# BLDC_ESC.net
KiCad netlist of a schematic drawn in EAGLE
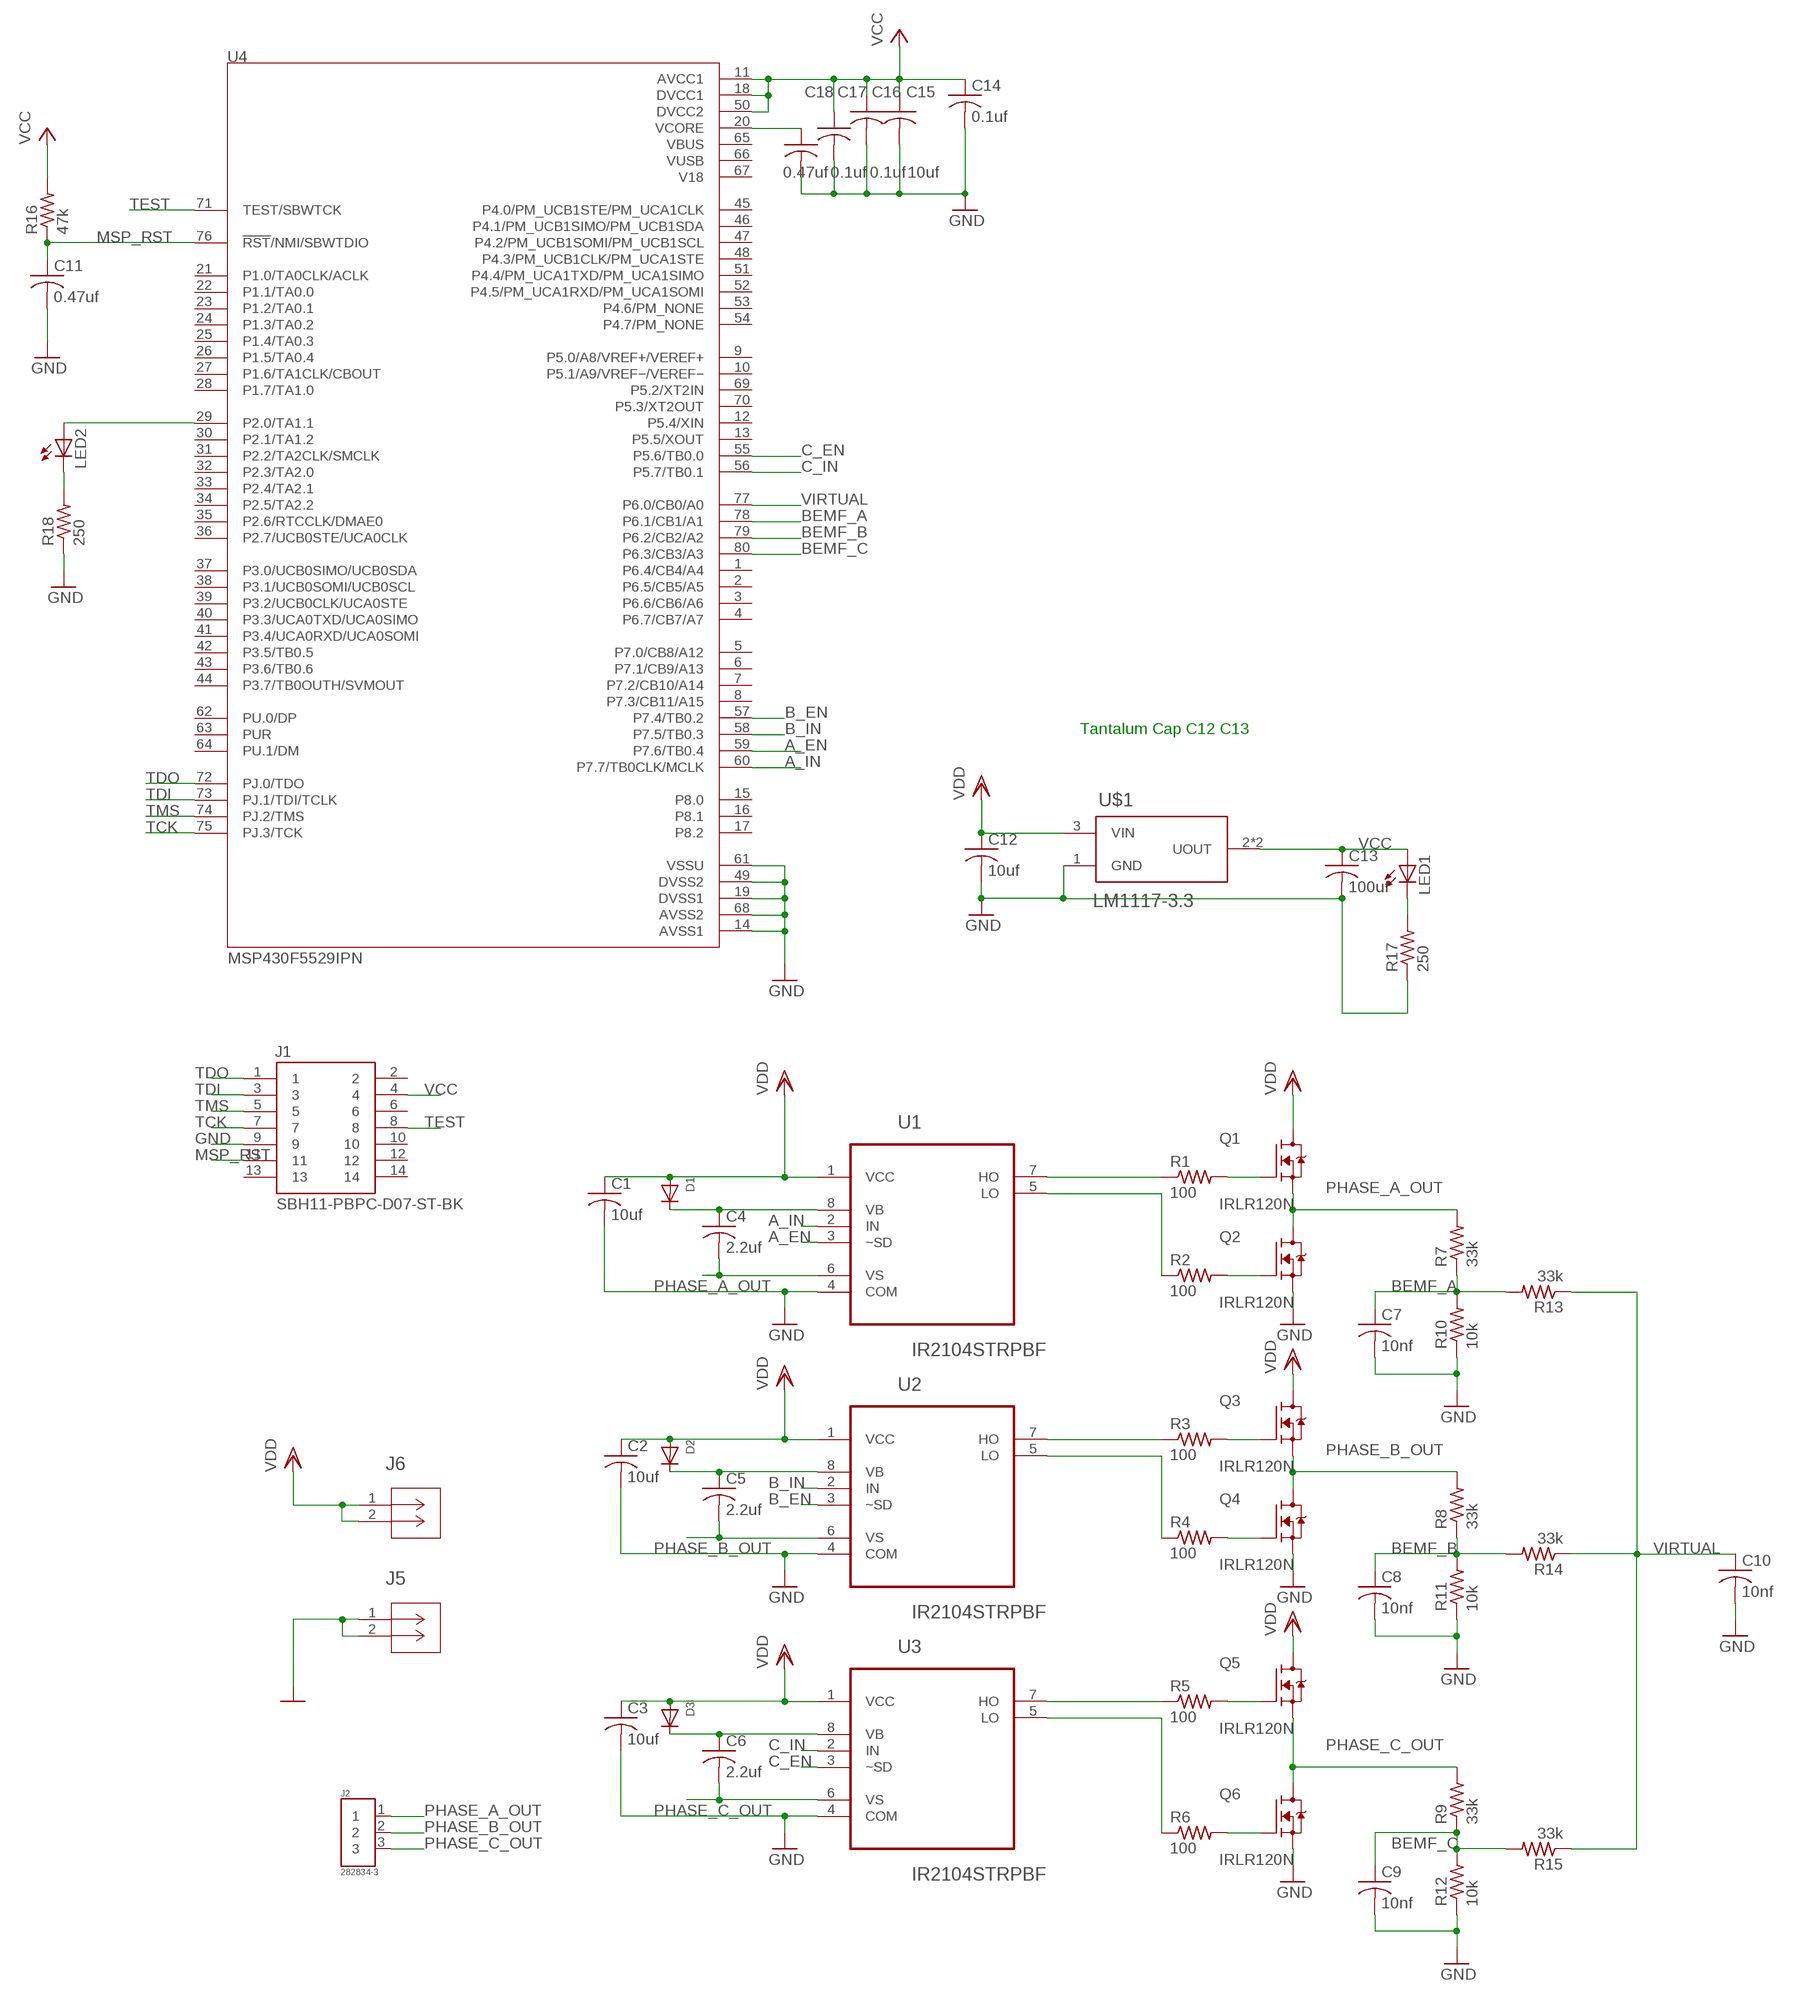
[diagram p0: schematic, sheet 1]

(export (version "E")
  (design (tool "Eeschema 10.0.6"))
  (components
    (comp (ref "C1")
      (value "10uf")
      (footprint "eagle-import:C0805K")
      (libsource (lib "eagle-import") (part "C-USC0805K"))
    )
    (comp (ref "C2")
      (value "10uf")
      (footprint "eagle-import:C0805K")
      (libsource (lib "eagle-import") (part "C-USC0805K"))
    )
    (comp (ref "C3")
      (value "10uf")
      (footprint "eagle-import:C0805K")
      (libsource (lib "eagle-import") (part "C-USC0805K"))
    )
    (comp (ref "C4")
      (value "2.2uf")
      (footprint "eagle-import:C0805K")
      (libsource (lib "eagle-import") (part "C-USC0805K"))
    )
    (comp (ref "C5")
      (value "2.2uf")
      (footprint "eagle-import:C0805K")
      (libsource (lib "eagle-import") (part "C-USC0805K"))
    )
    (comp (ref "C6")
      (value "2.2uf")
      (footprint "eagle-import:C0805K")
      (libsource (lib "eagle-import") (part "C-USC0805K"))
    )
    (comp (ref "C7")
      (value "10nf")
      (footprint "eagle-import:C0805")
      (libsource (lib "eagle-import") (part "rcl_334_C-USC0805"))
    )
    (comp (ref "C8")
      (value "10nf")
      (footprint "eagle-import:C0805")
      (libsource (lib "eagle-import") (part "rcl_334_C-USC0805"))
    )
    (comp (ref "C9")
      (value "10nf")
      (footprint "eagle-import:C0805")
      (libsource (lib "eagle-import") (part "rcl_334_C-USC0805"))
    )
    (comp (ref "C10")
      (value "10nf")
      (footprint "eagle-import:C0805")
      (libsource (lib "eagle-import") (part "rcl_334_C-USC0805"))
    )
    (comp (ref "C11")
      (value "0.47uf")
      (footprint "eagle-import:C0805")
      (libsource (lib "eagle-import") (part "rcl_334_C-USC0805"))
    )
    (comp (ref "C12")
      (value "10uf")
      (footprint "eagle-import:C0805")
      (libsource (lib "eagle-import") (part "C-USC0805"))
    )
    (comp (ref "C13")
      (value "100uf")
      (footprint "eagle-import:C0805")
      (libsource (lib "eagle-import") (part "C-USC0805"))
    )
    (comp (ref "C14")
      (value "0.1uf")
      (footprint "eagle-import:C0805")
      (libsource (lib "eagle-import") (part "C-USC0805"))
    )
    (comp (ref "C15")
      (value "10uf")
      (footprint "eagle-import:C0805")
      (libsource (lib "eagle-import") (part "C-USC0805"))
    )
    (comp (ref "C16")
      (value "0.1uf")
      (footprint "eagle-import:C0805")
      (libsource (lib "eagle-import") (part "C-USC0805"))
    )
    (comp (ref "C17")
      (value "0.1uf")
      (footprint "eagle-import:C0805")
      (libsource (lib "eagle-import") (part "C-USC0805"))
    )
    (comp (ref "C18")
      (value "0.47uf")
      (footprint "eagle-import:C0805")
      (libsource (lib "eagle-import") (part "C-USC0805"))
    )
    (comp (ref "D1")
      (value "DIODESOD-123")
      (footprint "eagle-import:SOD-123")
      (libsource (lib "eagle-import") (part "DIODESOD-123"))
    )
    (comp (ref "D2")
      (value "DIODESOD-123")
      (footprint "eagle-import:SOD-123")
      (libsource (lib "eagle-import") (part "DIODESOD-123"))
    )
    (comp (ref "D3")
      (value "DIODESOD-123")
      (footprint "eagle-import:SOD-123")
      (libsource (lib "eagle-import") (part "DIODESOD-123"))
    )
    (comp (ref "J1")
      (value "SBH11-PBPC-D07-ST-BK")
      (footprint "eagle-import:SULLINS_SBH11-PBPC-D07-ST-BK")
      (fields (field (name "DIGI-KEY_PART_NUMBER") "S9170-ND") (field (name "MF") "Sullins Connector"))
      (libsource (lib "eagle-import") (part "SBH11-PBPC-D07-ST-BK"))
    )
    (comp (ref "J2")
      (value "282834-3")
      (footprint "eagle-import:TE_282834-3")
      (fields (field (name "DIGI-KEY_PART_NUMBER") "A98334-ND") (field (name "MF") "TE Connectivity"))
      (libsource (lib "eagle-import") (part "282834-3"))
    )
    (comp (ref "J5")
      (value "105-1103-001")
      (footprint "eagle-import:CONN_105-1102-001")
      (fields (field (name "COPYRIGHT") "Copyright (C) 2018 Accelerated Designs. All rights reserved"))
      (libsource (lib "eagle-import") (part "105-1103-001"))
    )
    (comp (ref "J6")
      (value "105-1103-001")
      (footprint "eagle-import:CONN_105-1102-001")
      (fields (field (name "COPYRIGHT") "Copyright (C) 2018 Accelerated Designs. All rights reserved"))
      (libsource (lib "eagle-import") (part "105-1103-001"))
    )
    (comp (ref "LED1")
      (value "LEDCHIPLED_0805")
      (footprint "eagle-import:CHIPLED_0805")
      (libsource (lib "eagle-import") (part "LEDCHIPLED_0805"))
    )
    (comp (ref "LED2")
      (value "LEDCHIPLED_0805")
      (footprint "eagle-import:CHIPLED_0805")
      (libsource (lib "eagle-import") (part "LEDCHIPLED_0805"))
    )
    (comp (ref "Q1")
      (value "IRLR120N")
      (footprint "eagle-import:DPAK229P990X239-3N")
      (fields
        (field (name "DIGI-KEY_PART_NUMBER") "IRLR120NPBFCT-ND")
        (field (name "MF") "Infineon Technologies")
      )
      (libsource (lib "eagle-import") (part "IRLR120N"))
    )
    (comp (ref "Q2")
      (value "IRLR120N")
      (footprint "eagle-import:DPAK229P990X239-3N")
      (fields
        (field (name "DIGI-KEY_PART_NUMBER") "IRLR120NPBFCT-ND")
        (field (name "MF") "Infineon Technologies")
      )
      (libsource (lib "eagle-import") (part "IRLR120N"))
    )
    (comp (ref "Q3")
      (value "IRLR120N")
      (footprint "eagle-import:DPAK229P990X239-3N")
      (fields
        (field (name "DIGI-KEY_PART_NUMBER") "IRLR120NPBFCT-ND")
        (field (name "MF") "Infineon Technologies")
      )
      (libsource (lib "eagle-import") (part "IRLR120N"))
    )
    (comp (ref "Q4")
      (value "IRLR120N")
      (footprint "eagle-import:DPAK229P990X239-3N")
      (fields
        (field (name "DIGI-KEY_PART_NUMBER") "IRLR120NPBFCT-ND")
        (field (name "MF") "Infineon Technologies")
      )
      (libsource (lib "eagle-import") (part "IRLR120N"))
    )
    (comp (ref "Q5")
      (value "IRLR120N")
      (footprint "eagle-import:DPAK229P990X239-3N")
      (fields
        (field (name "DIGI-KEY_PART_NUMBER") "IRLR120NPBFCT-ND")
        (field (name "MF") "Infineon Technologies")
      )
      (libsource (lib "eagle-import") (part "IRLR120N"))
    )
    (comp (ref "Q6")
      (value "IRLR120N")
      (footprint "eagle-import:DPAK229P990X239-3N")
      (fields
        (field (name "DIGI-KEY_PART_NUMBER") "IRLR120NPBFCT-ND")
        (field (name "MF") "Infineon Technologies")
      )
      (libsource (lib "eagle-import") (part "IRLR120N"))
    )
    (comp (ref "R1")
      (value "100")
      (footprint "eagle-import:R0805")
      (libsource (lib "eagle-import") (part "R-US_R0805"))
    )
    (comp (ref "R2")
      (value "100")
      (footprint "eagle-import:R0805")
      (libsource (lib "eagle-import") (part "R-US_R0805"))
    )
    (comp (ref "R3")
      (value "100")
      (footprint "eagle-import:R0805")
      (libsource (lib "eagle-import") (part "R-US_R0805"))
    )
    (comp (ref "R4")
      (value "100")
      (footprint "eagle-import:R0805")
      (libsource (lib "eagle-import") (part "R-US_R0805"))
    )
    (comp (ref "R5")
      (value "100")
      (footprint "eagle-import:R0805")
      (libsource (lib "eagle-import") (part "R-US_R0805"))
    )
    (comp (ref "R6")
      (value "100")
      (footprint "eagle-import:R0805")
      (libsource (lib "eagle-import") (part "R-US_R0805"))
    )
    (comp (ref "R7")
      (value "33k")
      (footprint "eagle-import:R0805")
      (libsource (lib "eagle-import") (part "R-US_R0805"))
    )
    (comp (ref "R8")
      (value "33k")
      (footprint "eagle-import:R0805")
      (libsource (lib "eagle-import") (part "R-US_R0805"))
    )
    (comp (ref "R9")
      (value "33k")
      (footprint "eagle-import:R0805")
      (libsource (lib "eagle-import") (part "R-US_R0805"))
    )
    (comp (ref "R10")
      (value "10k")
      (footprint "eagle-import:R0805")
      (libsource (lib "eagle-import") (part "R-US_R0805"))
    )
    (comp (ref "R11")
      (value "10k")
      (footprint "eagle-import:R0805")
      (libsource (lib "eagle-import") (part "R-US_R0805"))
    )
    (comp (ref "R12")
      (value "10k")
      (footprint "eagle-import:R0805")
      (libsource (lib "eagle-import") (part "R-US_R0805"))
    )
    (comp (ref "R13")
      (value "33k")
      (footprint "eagle-import:R0805")
      (libsource (lib "eagle-import") (part "R-US_R0805"))
    )
    (comp (ref "R14")
      (value "33k")
      (footprint "eagle-import:R0805")
      (libsource (lib "eagle-import") (part "R-US_R0805"))
    )
    (comp (ref "R15")
      (value "33k")
      (footprint "eagle-import:R0805")
      (libsource (lib "eagle-import") (part "R-US_R0805"))
    )
    (comp (ref "R16")
      (value "47k")
      (footprint "eagle-import:M0805")
      (libsource (lib "eagle-import") (part "R-US_M0805"))
    )
    (comp (ref "R17")
      (value "250")
      (footprint "eagle-import:R0805")
      (libsource (lib "eagle-import") (part "R-US_R0805"))
    )
    (comp (ref "R18")
      (value "250")
      (footprint "eagle-import:R0805")
      (libsource (lib "eagle-import") (part "R-US_R0805"))
    )
    (comp (ref "U$1")
      (value "LM1117-3.3")
      (footprint "eagle-import:SOT-223")
      (fields (field (name "MF") "Texas Instruments"))
      (libsource (lib "eagle-import") (part "LM1117-3.3"))
    )
    (comp (ref "U1")
      (value "IR2104STRPBF")
      (footprint "eagle-import:SOIC127P600X175-8N")
      (fields
        (field (name "DIGI-KEY_PART_NUMBER") "IR2104SPBFCT-ND")
        (field (name "MF") "Infineon Technologies")
      )
      (libsource (lib "eagle-import") (part "IR2104STRPBF"))
    )
    (comp (ref "U2")
      (value "IR2104STRPBF")
      (footprint "eagle-import:SOIC127P600X175-8N")
      (fields
        (field (name "DIGI-KEY_PART_NUMBER") "IR2104SPBFCT-ND")
        (field (name "MF") "Infineon Technologies")
      )
      (libsource (lib "eagle-import") (part "IR2104STRPBF"))
    )
    (comp (ref "U3")
      (value "IR2104STRPBF")
      (footprint "eagle-import:SOIC127P600X175-8N")
      (fields
        (field (name "DIGI-KEY_PART_NUMBER") "IR2104SPBFCT-ND")
        (field (name "MF") "Infineon Technologies")
      )
      (libsource (lib "eagle-import") (part "IR2104STRPBF"))
    )
    (comp (ref "U4")
      (value "MSP430F5529IPN")
      (footprint "eagle-import:QFP50P1400X1400X160-80N")
      (fields (field (name "MF") "Texas Instruments"))
      (libsource (lib "eagle-import") (part "MSP430F5529IPN"))
    )
  )
  (nets
    (net (code "1") (name "/A_EN") (class "Default")
      (node (ref "U1") (pin "3") (pinfunction "~{SD}_3") (pintype "input"))
      (node (ref "U4") (pin "59") (pinfunction "P7.6/TB0.4_59") (pintype "bidirectional"))
    )
    (net (code "2") (name "/A_IN") (class "Default")
      (node (ref "U1") (pin "2") (pinfunction "IN_2") (pintype "input"))
      (node (ref "U4") (pin "60") (pinfunction "P7.7/TB0CLK/MCLK_60") (pintype "bidirectional"))
    )
    (net (code "3") (name "/BEMF_A") (class "Default")
      (node (ref "C7") (pin "1") (pinfunction "1_1") (pintype "passive"))
      (node (ref "R10") (pin "2") (pinfunction "2_2") (pintype "passive"))
      (node (ref "R13") (pin "2") (pinfunction "2_2") (pintype "passive"))
      (node (ref "R7") (pin "1") (pinfunction "1_1") (pintype "passive"))
      (node (ref "U4") (pin "78") (pinfunction "P6.1/CB1/A1_78") (pintype "bidirectional"))
    )
    (net (code "4") (name "/BEMF_B") (class "Default")
      (node (ref "C8") (pin "1") (pinfunction "1_1") (pintype "passive"))
      (node (ref "R11") (pin "2") (pinfunction "2_2") (pintype "passive"))
      (node (ref "R14") (pin "2") (pinfunction "2_2") (pintype "passive"))
      (node (ref "R8") (pin "1") (pinfunction "1_1") (pintype "passive"))
      (node (ref "U4") (pin "79") (pinfunction "P6.2/CB2/A2_79") (pintype "bidirectional"))
    )
    (net (code "5") (name "/BEMF_C") (class "Default")
      (node (ref "C9") (pin "1") (pinfunction "1_1") (pintype "passive"))
      (node (ref "R12") (pin "2") (pinfunction "2_2") (pintype "passive"))
      (node (ref "R15") (pin "2") (pinfunction "2_2") (pintype "passive"))
      (node (ref "R9") (pin "1") (pinfunction "1_1") (pintype "passive"))
      (node (ref "U4") (pin "80") (pinfunction "P6.3/CB3/A3_80") (pintype "bidirectional"))
    )
    (net (code "6") (name "/B_EN") (class "Default")
      (node (ref "U2") (pin "3") (pinfunction "~{SD}_3") (pintype "input"))
      (node (ref "U4") (pin "57") (pinfunction "P7.4/TB0.2_57") (pintype "bidirectional"))
    )
    (net (code "7") (name "/B_IN") (class "Default")
      (node (ref "U2") (pin "2") (pinfunction "IN_2") (pintype "input"))
      (node (ref "U4") (pin "58") (pinfunction "P7.5/TB0.3_58") (pintype "bidirectional"))
    )
    (net (code "8") (name "/C_EN") (class "Default")
      (node (ref "U3") (pin "3") (pinfunction "~{SD}_3") (pintype "input"))
      (node (ref "U4") (pin "55") (pinfunction "P5.6/TB0.0_55") (pintype "bidirectional"))
    )
    (net (code "9") (name "/C_IN") (class "Default")
      (node (ref "U3") (pin "2") (pinfunction "IN_2") (pintype "input"))
      (node (ref "U4") (pin "56") (pinfunction "P5.7/TB0.1_56") (pintype "bidirectional"))
    )
    (net (code "10") (name "/MSP_RST") (class "Default")
      (node (ref "C11") (pin "1") (pinfunction "1_1") (pintype "passive"))
      (node (ref "J1") (pin "11") (pinfunction "11_11") (pintype "passive"))
      (node (ref "R16") (pin "1") (pinfunction "1_1") (pintype "passive"))
      (node (ref "U4") (pin "76") (pinfunction "~{RST}/NMI/SBWTDIO_76") (pintype "bidirectional"))
    )
    (net (code "11") (name "/PHASE_A_OUT") (class "Default")
      (node (ref "C4") (pin "2") (pinfunction "2_2") (pintype "passive"))
      (node (ref "J2") (pin "1") (pinfunction "1_1") (pintype "passive"))
      (node (ref "Q1") (pin "2") (pinfunction "S_2") (pintype "passive"))
      (node (ref "Q2") (pin "3") (pinfunction "D_3") (pintype "passive"))
      (node (ref "R7") (pin "2") (pinfunction "2_2") (pintype "passive"))
      (node (ref "U1") (pin "6") (pinfunction "VS_6") (pintype "power_in"))
    )
    (net (code "12") (name "/PHASE_B_OUT") (class "Default")
      (node (ref "C5") (pin "2") (pinfunction "2_2") (pintype "passive"))
      (node (ref "J2") (pin "2") (pinfunction "2_2") (pintype "passive"))
      (node (ref "Q3") (pin "2") (pinfunction "S_2") (pintype "passive"))
      (node (ref "Q4") (pin "3") (pinfunction "D_3") (pintype "passive"))
      (node (ref "R8") (pin "2") (pinfunction "2_2") (pintype "passive"))
      (node (ref "U2") (pin "6") (pinfunction "VS_6") (pintype "power_in"))
    )
    (net (code "13") (name "/PHASE_C_OUT") (class "Default")
      (node (ref "C6") (pin "2") (pinfunction "2_2") (pintype "passive"))
      (node (ref "J2") (pin "3") (pinfunction "3_3") (pintype "passive"))
      (node (ref "Q5") (pin "2") (pinfunction "S_2") (pintype "passive"))
      (node (ref "Q6") (pin "3") (pinfunction "D_3") (pintype "passive"))
      (node (ref "R9") (pin "2") (pinfunction "2_2") (pintype "passive"))
      (node (ref "U3") (pin "6") (pinfunction "VS_6") (pintype "power_in"))
    )
    (net (code "14") (name "/TCK") (class "Default")
      (node (ref "J1") (pin "7") (pinfunction "7_7") (pintype "passive"))
      (node (ref "U4") (pin "75") (pinfunction "PJ.3/TCK_75") (pintype "bidirectional"))
    )
    (net (code "15") (name "/TDI") (class "Default")
      (node (ref "J1") (pin "3") (pinfunction "3_3") (pintype "passive"))
      (node (ref "U4") (pin "73") (pinfunction "PJ.1/TDI/TCLK_73") (pintype "bidirectional"))
    )
    (net (code "16") (name "/TDO") (class "Default")
      (node (ref "J1") (pin "1") (pinfunction "1_1") (pintype "passive"))
      (node (ref "U4") (pin "72") (pinfunction "PJ.0/TDO_72") (pintype "bidirectional"))
    )
    (net (code "17") (name "/TEST") (class "Default")
      (node (ref "J1") (pin "8") (pinfunction "8_8") (pintype "passive"))
      (node (ref "U4") (pin "71") (pinfunction "TEST/SBWTCK_71") (pintype "input"))
    )
    (net (code "18") (name "/TMS") (class "Default")
      (node (ref "J1") (pin "5") (pinfunction "5_5") (pintype "passive"))
      (node (ref "U4") (pin "74") (pinfunction "PJ.2/TMS_74") (pintype "bidirectional"))
    )
    (net (code "19") (name "/V18") (class "Default")
      (node (ref "U4") (pin "67") (pinfunction "V18_67") (pintype "power_in"))
    )
    (net (code "20") (name "/VBUS") (class "Default")
      (node (ref "U4") (pin "65") (pinfunction "VBUS_65") (pintype "power_in"))
    )
    (net (code "21") (name "/VIRTUAL") (class "Default")
      (node (ref "C10") (pin "1") (pinfunction "1_1") (pintype "passive"))
      (node (ref "R13") (pin "1") (pinfunction "1_1") (pintype "passive"))
      (node (ref "R14") (pin "1") (pinfunction "1_1") (pintype "passive"))
      (node (ref "R15") (pin "1") (pinfunction "1_1") (pintype "passive"))
      (node (ref "U4") (pin "77") (pinfunction "P6.0/CB0/A0_77") (pintype "bidirectional"))
    )
    (net (code "22") (name "/VUSB") (class "Default")
      (node (ref "U4") (pin "66") (pinfunction "VUSB_66") (pintype "power_in"))
    )
    (net (code "23") (name "GND") (class "Default")
      (node (ref "C1") (pin "2") (pinfunction "2_2") (pintype "passive"))
      (node (ref "C10") (pin "2") (pinfunction "2_2") (pintype "passive"))
      (node (ref "C11") (pin "2") (pinfunction "2_2") (pintype "passive"))
      (node (ref "C12") (pin "2") (pinfunction "2_2") (pintype "passive"))
      (node (ref "C13") (pin "2") (pinfunction "2_2") (pintype "passive"))
      (node (ref "C14") (pin "2") (pinfunction "2_2") (pintype "passive"))
      (node (ref "C15") (pin "2") (pinfunction "2_2") (pintype "passive"))
      (node (ref "C16") (pin "2") (pinfunction "2_2") (pintype "passive"))
      (node (ref "C17") (pin "2") (pinfunction "2_2") (pintype "passive"))
      (node (ref "C18") (pin "2") (pinfunction "2_2") (pintype "passive"))
      (node (ref "C2") (pin "2") (pinfunction "2_2") (pintype "passive"))
      (node (ref "C3") (pin "2") (pinfunction "2_2") (pintype "passive"))
      (node (ref "C7") (pin "2") (pinfunction "2_2") (pintype "passive"))
      (node (ref "C8") (pin "2") (pinfunction "2_2") (pintype "passive"))
      (node (ref "C9") (pin "2") (pinfunction "2_2") (pintype "passive"))
      (node (ref "J1") (pin "9") (pinfunction "9_9") (pintype "passive"))
      (node (ref "J5") (pin "1") (pinfunction "1_1") (pintype "passive"))
      (node (ref "J5") (pin "2") (pinfunction "2_2") (pintype "passive"))
      (node (ref "Q2") (pin "2") (pinfunction "S_2") (pintype "passive"))
      (node (ref "Q4") (pin "2") (pinfunction "S_2") (pintype "passive"))
      (node (ref "Q6") (pin "2") (pinfunction "S_2") (pintype "passive"))
      (node (ref "R10") (pin "1") (pinfunction "1_1") (pintype "passive"))
      (node (ref "R11") (pin "1") (pinfunction "1_1") (pintype "passive"))
      (node (ref "R12") (pin "1") (pinfunction "1_1") (pintype "passive"))
      (node (ref "R17") (pin "1") (pinfunction "1_1") (pintype "passive"))
      (node (ref "R18") (pin "1") (pinfunction "1_1") (pintype "passive"))
      (node (ref "U$1") (pin "1") (pinfunction "GND_1") (pintype "passive"))
      (node (ref "U1") (pin "4") (pinfunction "COM_4") (pintype "passive"))
      (node (ref "U2") (pin "4") (pinfunction "COM_4") (pintype "passive"))
      (node (ref "U3") (pin "4") (pinfunction "COM_4") (pintype "passive"))
      (node (ref "U4") (pin "14") (pinfunction "AVSS1_14") (pintype "power_in"))
      (node (ref "U4") (pin "19") (pinfunction "DVSS1_19") (pintype "power_in"))
      (node (ref "U4") (pin "49") (pinfunction "DVSS2_49") (pintype "power_in"))
      (node (ref "U4") (pin "61") (pinfunction "VSSU_61") (pintype "power_in"))
      (node (ref "U4") (pin "68") (pinfunction "AVSS2_68") (pintype "power_in"))
    )
    (net (code "24") (name "Net-(LED1-PadC)") (class "Default")
      (node (ref "LED1") (pin "C") (pinfunction "C_C") (pintype "passive"))
      (node (ref "R17") (pin "2") (pinfunction "2_2") (pintype "passive"))
    )
    (net (code "25") (name "Net-(LED2-PadC)") (class "Default")
      (node (ref "LED2") (pin "C") (pinfunction "C_C") (pintype "passive"))
      (node (ref "R18") (pin "2") (pinfunction "2_2") (pintype "passive"))
    )
    (net (code "26") (name "Net-(Q1-G)") (class "Default")
      (node (ref "Q1") (pin "1") (pinfunction "G_1") (pintype "passive"))
      (node (ref "R1") (pin "2") (pinfunction "2_2") (pintype "passive"))
    )
    (net (code "27") (name "Net-(Q2-G)") (class "Default")
      (node (ref "Q2") (pin "1") (pinfunction "G_1") (pintype "passive"))
      (node (ref "R2") (pin "2") (pinfunction "2_2") (pintype "passive"))
    )
    (net (code "28") (name "Net-(Q3-G)") (class "Default")
      (node (ref "Q3") (pin "1") (pinfunction "G_1") (pintype "passive"))
      (node (ref "R3") (pin "2") (pinfunction "2_2") (pintype "passive"))
    )
    (net (code "29") (name "Net-(Q4-G)") (class "Default")
      (node (ref "Q4") (pin "1") (pinfunction "G_1") (pintype "passive"))
      (node (ref "R4") (pin "2") (pinfunction "2_2") (pintype "passive"))
    )
    (net (code "30") (name "Net-(Q5-G)") (class "Default")
      (node (ref "Q5") (pin "1") (pinfunction "G_1") (pintype "passive"))
      (node (ref "R5") (pin "2") (pinfunction "2_2") (pintype "passive"))
    )
    (net (code "31") (name "Net-(Q6-G)") (class "Default")
      (node (ref "Q6") (pin "1") (pinfunction "G_1") (pintype "passive"))
      (node (ref "R6") (pin "2") (pinfunction "2_2") (pintype "passive"))
    )
    (net (code "32") (name "Net-(U1-HO)") (class "Default")
      (node (ref "R1") (pin "1") (pinfunction "1_1") (pintype "passive"))
      (node (ref "U1") (pin "7") (pinfunction "HO_7") (pintype "output"))
    )
    (net (code "33") (name "Net-(U1-LO)") (class "Default")
      (node (ref "R2") (pin "1") (pinfunction "1_1") (pintype "passive"))
      (node (ref "U1") (pin "5") (pinfunction "LO_5") (pintype "output"))
    )
    (net (code "34") (name "Net-(U1-VB)") (class "Default")
      (node (ref "C4") (pin "1") (pinfunction "1_1") (pintype "passive"))
      (node (ref "D1") (pin "C") (pinfunction "C_C") (pintype "passive"))
      (node (ref "U1") (pin "8") (pinfunction "VB_8") (pintype "power_in"))
    )
    (net (code "35") (name "Net-(U2-HO)") (class "Default")
      (node (ref "R3") (pin "1") (pinfunction "1_1") (pintype "passive"))
      (node (ref "U2") (pin "7") (pinfunction "HO_7") (pintype "output"))
    )
    (net (code "36") (name "Net-(U2-LO)") (class "Default")
      (node (ref "R4") (pin "1") (pinfunction "1_1") (pintype "passive"))
      (node (ref "U2") (pin "5") (pinfunction "LO_5") (pintype "output"))
    )
    (net (code "37") (name "Net-(U2-VB)") (class "Default")
      (node (ref "C5") (pin "1") (pinfunction "1_1") (pintype "passive"))
      (node (ref "D2") (pin "C") (pinfunction "C_C") (pintype "passive"))
      (node (ref "U2") (pin "8") (pinfunction "VB_8") (pintype "power_in"))
    )
    (net (code "38") (name "Net-(U3-HO)") (class "Default")
      (node (ref "R5") (pin "1") (pinfunction "1_1") (pintype "passive"))
      (node (ref "U3") (pin "7") (pinfunction "HO_7") (pintype "output"))
    )
    (net (code "39") (name "Net-(U3-LO)") (class "Default")
      (node (ref "R6") (pin "1") (pinfunction "1_1") (pintype "passive"))
      (node (ref "U3") (pin "5") (pinfunction "LO_5") (pintype "output"))
    )
    (net (code "40") (name "Net-(U3-VB)") (class "Default")
      (node (ref "C6") (pin "1") (pinfunction "1_1") (pintype "passive"))
      (node (ref "D3") (pin "C") (pinfunction "C_C") (pintype "passive"))
      (node (ref "U3") (pin "8") (pinfunction "VB_8") (pintype "power_in"))
    )
    (net (code "41") (name "Net-(U4-P2.0{slash}TA1.1)") (class "Default")
      (node (ref "LED2") (pin "A") (pinfunction "A_A") (pintype "passive"))
      (node (ref "U4") (pin "29") (pinfunction "P2.0/TA1.1_29") (pintype "bidirectional"))
    )
    (net (code "42") (name "Net-(U4-VCORE)") (class "Default")
      (node (ref "C18") (pin "1") (pinfunction "1_1") (pintype "passive"))
      (node (ref "U4") (pin "20") (pinfunction "VCORE_20") (pintype "power_in"))
    )
    (net (code "43") (name "VCC") (class "Default")
      (node (ref "C13") (pin "1") (pinfunction "1_1") (pintype "passive"))
      (node (ref "C14") (pin "1") (pinfunction "1_1") (pintype "passive"))
      (node (ref "C15") (pin "1") (pinfunction "1_1") (pintype "passive"))
      (node (ref "C16") (pin "1") (pinfunction "1_1") (pintype "passive"))
      (node (ref "C17") (pin "1") (pinfunction "1_1") (pintype "passive"))
      (node (ref "J1") (pin "4") (pinfunction "4_4") (pintype "passive"))
      (node (ref "LED1") (pin "A") (pinfunction "A_A") (pintype "passive"))
      (node (ref "R16") (pin "2") (pinfunction "2_2") (pintype "passive"))
      (node (ref "U$1") (pin "2") (pinfunction "UOUT_2") (pintype "output"))
      (node (ref "U$1") (pin "4") (pinfunction "UOUT_4") (pintype "output"))
      (node (ref "U4") (pin "11") (pinfunction "AVCC1_11") (pintype "power_in"))
      (node (ref "U4") (pin "18") (pinfunction "DVCC1_18") (pintype "power_in"))
      (node (ref "U4") (pin "50") (pinfunction "DVCC2_50") (pintype "power_in"))
    )
    (net (code "44") (name "VDD") (class "Default")
      (node (ref "C1") (pin "1") (pinfunction "1_1") (pintype "passive"))
      (node (ref "C12") (pin "1") (pinfunction "1_1") (pintype "passive"))
      (node (ref "C2") (pin "1") (pinfunction "1_1") (pintype "passive"))
      (node (ref "C3") (pin "1") (pinfunction "1_1") (pintype "passive"))
      (node (ref "D1") (pin "A") (pinfunction "A_A") (pintype "passive"))
      (node (ref "D2") (pin "A") (pinfunction "A_A") (pintype "passive"))
      (node (ref "D3") (pin "A") (pinfunction "A_A") (pintype "passive"))
      (node (ref "J6") (pin "1") (pinfunction "1_1") (pintype "passive"))
      (node (ref "J6") (pin "2") (pinfunction "2_2") (pintype "passive"))
      (node (ref "Q1") (pin "3") (pinfunction "D_3") (pintype "passive"))
      (node (ref "Q3") (pin "3") (pinfunction "D_3") (pintype "passive"))
      (node (ref "Q5") (pin "3") (pinfunction "D_3") (pintype "passive"))
      (node (ref "U$1") (pin "3") (pinfunction "VIN_3") (pintype "bidirectional"))
      (node (ref "U1") (pin "1") (pinfunction "VCC_1") (pintype "power_in"))
      (node (ref "U2") (pin "1") (pinfunction "VCC_1") (pintype "power_in"))
      (node (ref "U3") (pin "1") (pinfunction "VCC_1") (pintype "power_in"))
    )
    (net (code "45") (name "unconnected-(J1-Pad2)") (class "Default")
      (node (ref "J1") (pin "2") (pinfunction "2_2") (pintype "passive"))
    )
    (net (code "46") (name "unconnected-(J1-Pad6)") (class "Default")
      (node (ref "J1") (pin "6") (pinfunction "6_6") (pintype "passive"))
    )
    (net (code "47") (name "unconnected-(J1-Pad10)") (class "Default")
      (node (ref "J1") (pin "10") (pinfunction "10_10") (pintype "passive"))
    )
    (net (code "48") (name "unconnected-(J1-Pad12)") (class "Default")
      (node (ref "J1") (pin "12") (pinfunction "12_12") (pintype "passive"))
    )
    (net (code "49") (name "unconnected-(J1-Pad13)") (class "Default")
      (node (ref "J1") (pin "13") (pinfunction "13_13") (pintype "passive"))
    )
    (net (code "50") (name "unconnected-(J1-Pad14)") (class "Default")
      (node (ref "J1") (pin "14") (pinfunction "14_14") (pintype "passive"))
    )
    (net (code "51") (name "unconnected-(U4-P1.0{slash}TA0CLK{slash}ACLK-Pad21)") (class "Default")
      (node (ref "U4") (pin "21") (pinfunction "P1.0/TA0CLK/ACLK_21") (pintype "bidirectional"))
    )
    (net (code "52") (name "unconnected-(U4-P1.1{slash}TA0.0-Pad22)") (class "Default")
      (node (ref "U4") (pin "22") (pinfunction "P1.1/TA0.0_22") (pintype "bidirectional"))
    )
    (net (code "53") (name "unconnected-(U4-P1.2{slash}TA0.1-Pad23)") (class "Default")
      (node (ref "U4") (pin "23") (pinfunction "P1.2/TA0.1_23") (pintype "bidirectional"))
    )
    (net (code "54") (name "unconnected-(U4-P1.3{slash}TA0.2-Pad24)") (class "Default")
      (node (ref "U4") (pin "24") (pinfunction "P1.3/TA0.2_24") (pintype "bidirectional"))
    )
    (net (code "55") (name "unconnected-(U4-P1.4{slash}TA0.3-Pad25)") (class "Default")
      (node (ref "U4") (pin "25") (pinfunction "P1.4/TA0.3_25") (pintype "bidirectional"))
    )
    (net (code "56") (name "unconnected-(U4-P1.5{slash}TA0.4-Pad26)") (class "Default")
      (node (ref "U4") (pin "26") (pinfunction "P1.5/TA0.4_26") (pintype "bidirectional"))
    )
    (net (code "57") (name "unconnected-(U4-P1.6{slash}TA1CLK{slash}CBOUT-Pad27)") (class "Default")
      (node (ref "U4") (pin "27") (pinfunction "P1.6/TA1CLK/CBOUT_27") (pintype "bidirectional"))
    )
    (net (code "58") (name "unconnected-(U4-P1.7{slash}TA1.0-Pad28)") (class "Default")
      (node (ref "U4") (pin "28") (pinfunction "P1.7/TA1.0_28") (pintype "bidirectional"))
    )
    (net (code "59") (name "unconnected-(U4-P2.1{slash}TA1.2-Pad30)") (class "Default")
      (node (ref "U4") (pin "30") (pinfunction "P2.1/TA1.2_30") (pintype "bidirectional"))
    )
    (net (code "60") (name "unconnected-(U4-P2.2{slash}TA2CLK{slash}SMCLK-Pad31)") (class "Default")
      (node (ref "U4") (pin "31") (pinfunction "P2.2/TA2CLK/SMCLK_31") (pintype "bidirectional"))
    )
    (net (code "61") (name "unconnected-(U4-P2.3{slash}TA2.0-Pad32)") (class "Default")
      (node (ref "U4") (pin "32") (pinfunction "P2.3/TA2.0_32") (pintype "bidirectional"))
    )
    (net (code "62") (name "unconnected-(U4-P2.4{slash}TA2.1-Pad33)") (class "Default")
      (node (ref "U4") (pin "33") (pinfunction "P2.4/TA2.1_33") (pintype "bidirectional"))
    )
    (net (code "63") (name "unconnected-(U4-P2.5{slash}TA2.2-Pad34)") (class "Default")
      (node (ref "U4") (pin "34") (pinfunction "P2.5/TA2.2_34") (pintype "bidirectional"))
    )
    (net (code "64") (name "unconnected-(U4-P2.6{slash}RTCCLK{slash}DMAE0-Pad35)") (class "Default")
      (node (ref "U4") (pin "35") (pinfunction "P2.6/RTCCLK/DMAE0_35") (pintype "bidirectional"))
    )
    (net (code "65") (name "unconnected-(U4-P2.7{slash}UCB0STE{slash}UCA0CLK-Pad36)") (class "Default")
      (node (ref "U4") (pin "36") (pinfunction "P2.7/UCB0STE/UCA0CLK_36") (pintype "bidirectional"))
    )
    (net (code "66") (name "unconnected-(U4-P3.0{slash}UCB0SIMO{slash}UCB0SDA-Pad37)") (class "Default")
      (node (ref "U4") (pin "37") (pinfunction "P3.0/UCB0SIMO/UCB0SDA_37") (pintype "bidirectional"))
    )
    (net (code "67") (name "unconnected-(U4-P3.1{slash}UCB0SOMI{slash}UCB0SCL-Pad38)") (class "Default")
      (node (ref "U4") (pin "38") (pinfunction "P3.1/UCB0SOMI/UCB0SCL_38") (pintype "bidirectional"))
    )
    (net (code "68") (name "unconnected-(U4-P3.2{slash}UCB0CLK{slash}UCA0STE-Pad39)") (class "Default")
      (node (ref "U4") (pin "39") (pinfunction "P3.2/UCB0CLK/UCA0STE_39") (pintype "bidirectional"))
    )
    (net (code "69") (name "unconnected-(U4-P3.3{slash}UCA0TXD{slash}UCA0SIMO-Pad40)") (class "Default")
      (node (ref "U4") (pin "40") (pinfunction "P3.3/UCA0TXD/UCA0SIMO_40") (pintype "bidirectional"))
    )
    (net (code "70") (name "unconnected-(U4-P3.4{slash}UCA0RXD{slash}UCA0SOMI-Pad41)") (class "Default")
      (node (ref "U4") (pin "41") (pinfunction "P3.4/UCA0RXD/UCA0SOMI_41") (pintype "bidirectional"))
    )
    (net (code "71") (name "unconnected-(U4-P3.5{slash}TB0.5-Pad42)") (class "Default")
      (node (ref "U4") (pin "42") (pinfunction "P3.5/TB0.5_42") (pintype "bidirectional"))
    )
    (net (code "72") (name "unconnected-(U4-P3.6{slash}TB0.6-Pad43)") (class "Default")
      (node (ref "U4") (pin "43") (pinfunction "P3.6/TB0.6_43") (pintype "bidirectional"))
    )
    (net (code "73") (name "unconnected-(U4-P3.7{slash}TB0OUTH{slash}SVMOUT-Pad44)") (class "Default")
      (node (ref "U4") (pin "44") (pinfunction "P3.7/TB0OUTH/SVMOUT_44") (pintype "bidirectional"))
    )
    (net (code "74") (name "unconnected-(U4-P4.0{slash}PM_UCB1STE{slash}PM_UCA1CLK-Pad45)") (class "Default")
      (node (ref "U4") (pin "45") (pinfunction "P4.0/PM_UCB1STE/PM_UCA1CLK_45") (pintype "bidirectional"))
    )
    (net (code "75") (name "unconnected-(U4-P4.1{slash}PM_UCB1SIMO{slash}PM_UCB1SDA-Pad46)") (class "Default")
      (node (ref "U4") (pin "46") (pinfunction "P4.1/PM_UCB1SIMO/PM_UCB1SDA_46") (pintype "bidirectional"))
    )
    (net (code "76") (name "unconnected-(U4-P4.2{slash}PM_UCB1SOMI{slash}PM_UCB1SCL-Pad47)") (class "Default")
      (node (ref "U4") (pin "47") (pinfunction "P4.2/PM_UCB1SOMI/PM_UCB1SCL_47") (pintype "bidirectional"))
    )
    (net (code "77") (name "unconnected-(U4-P4.3{slash}PM_UCB1CLK{slash}PM_UCA1STE-Pad48)") (class "Default")
      (node (ref "U4") (pin "48") (pinfunction "P4.3/PM_UCB1CLK/PM_UCA1STE_48") (pintype "bidirectional"))
    )
    (net (code "78") (name "unconnected-(U4-P4.4{slash}PM_UCA1TXD{slash}PM_UCA1SIMO-Pad51)") (class "Default")
      (node (ref "U4") (pin "51") (pinfunction "P4.4/PM_UCA1TXD/PM_UCA1SIMO_51") (pintype "bidirectional"))
    )
    (net (code "79") (name "unconnected-(U4-P4.5{slash}PM_UCA1RXD{slash}PM_UCA1SOMI-Pad52)") (class "Default")
      (node (ref "U4") (pin "52") (pinfunction "P4.5/PM_UCA1RXD/PM_UCA1SOMI_52") (pintype "bidirectional"))
    )
    (net (code "80") (name "unconnected-(U4-P4.6{slash}PM_NONE-Pad53)") (class "Default")
      (node (ref "U4") (pin "53") (pinfunction "P4.6/PM_NONE_53") (pintype "bidirectional"))
    )
    (net (code "81") (name "unconnected-(U4-P4.7{slash}PM_NONE-Pad54)") (class "Default")
      (node (ref "U4") (pin "54") (pinfunction "P4.7/PM_NONE_54") (pintype "bidirectional"))
    )
    (net (code "82") (name "unconnected-(U4-P5.0{slash}A8{slash}VREF+{slash}VEREF+-Pad9)") (class "Default")
      (node (ref "U4") (pin "9") (pinfunction "P5.0/A8/VREF+/VEREF+_9") (pintype "bidirectional"))
    )
    (net (code "83") (name "unconnected-(U4-P5.1{slash}A9{slash}VREF−{slash}VEREF−-Pad10)") (class "Default")
      (node (ref "U4") (pin "10") (pinfunction "P5.1/A9/VREF−/VEREF−_10") (pintype "bidirectional"))
    )
    (net (code "84") (name "unconnected-(U4-P5.2{slash}XT2IN-Pad69)") (class "Default")
      (node (ref "U4") (pin "69") (pinfunction "P5.2/XT2IN_69") (pintype "bidirectional"))
    )
    (net (code "85") (name "unconnected-(U4-P5.3{slash}XT2OUT-Pad70)") (class "Default")
      (node (ref "U4") (pin "70") (pinfunction "P5.3/XT2OUT_70") (pintype "bidirectional"))
    )
    (net (code "86") (name "unconnected-(U4-P5.4{slash}XIN-Pad12)") (class "Default")
      (node (ref "U4") (pin "12") (pinfunction "P5.4/XIN_12") (pintype "bidirectional"))
    )
    (net (code "87") (name "unconnected-(U4-P5.5{slash}XOUT-Pad13)") (class "Default")
      (node (ref "U4") (pin "13") (pinfunction "P5.5/XOUT_13") (pintype "bidirectional"))
    )
    (net (code "88") (name "unconnected-(U4-P6.4{slash}CB4{slash}A4-Pad1)") (class "Default")
      (node (ref "U4") (pin "1") (pinfunction "P6.4/CB4/A4_1") (pintype "bidirectional"))
    )
    (net (code "89") (name "unconnected-(U4-P6.5{slash}CB5{slash}A5-Pad2)") (class "Default")
      (node (ref "U4") (pin "2") (pinfunction "P6.5/CB5/A5_2") (pintype "bidirectional"))
    )
    (net (code "90") (name "unconnected-(U4-P6.6{slash}CB6{slash}A6-Pad3)") (class "Default")
      (node (ref "U4") (pin "3") (pinfunction "P6.6/CB6/A6_3") (pintype "bidirectional"))
    )
    (net (code "91") (name "unconnected-(U4-P6.7{slash}CB7{slash}A7-Pad4)") (class "Default")
      (node (ref "U4") (pin "4") (pinfunction "P6.7/CB7/A7_4") (pintype "bidirectional"))
    )
    (net (code "92") (name "unconnected-(U4-P7.0{slash}CB8{slash}A12-Pad5)") (class "Default")
      (node (ref "U4") (pin "5") (pinfunction "P7.0/CB8/A12_5") (pintype "bidirectional"))
    )
    (net (code "93") (name "unconnected-(U4-P7.1{slash}CB9{slash}A13-Pad6)") (class "Default")
      (node (ref "U4") (pin "6") (pinfunction "P7.1/CB9/A13_6") (pintype "bidirectional"))
    )
    (net (code "94") (name "unconnected-(U4-P7.2{slash}CB10{slash}A14-Pad7)") (class "Default")
      (node (ref "U4") (pin "7") (pinfunction "P7.2/CB10/A14_7") (pintype "bidirectional"))
    )
    (net (code "95") (name "unconnected-(U4-P7.3{slash}CB11{slash}A15-Pad8)") (class "Default")
      (node (ref "U4") (pin "8") (pinfunction "P7.3/CB11/A15_8") (pintype "bidirectional"))
    )
    (net (code "96") (name "unconnected-(U4-P8.0-Pad15)") (class "Default")
      (node (ref "U4") (pin "15") (pinfunction "P8.0_15") (pintype "bidirectional"))
    )
    (net (code "97") (name "unconnected-(U4-P8.1-Pad16)") (class "Default")
      (node (ref "U4") (pin "16") (pinfunction "P8.1_16") (pintype "bidirectional"))
    )
    (net (code "98") (name "unconnected-(U4-P8.2-Pad17)") (class "Default")
      (node (ref "U4") (pin "17") (pinfunction "P8.2_17") (pintype "bidirectional"))
    )
    (net (code "99") (name "unconnected-(U4-PU.0{slash}DP-Pad62)") (class "Default")
      (node (ref "U4") (pin "62") (pinfunction "PU.0/DP_62") (pintype "bidirectional"))
    )
    (net (code "100") (name "unconnected-(U4-PU.1{slash}DM-Pad64)") (class "Default")
      (node (ref "U4") (pin "64") (pinfunction "PU.1/DM_64") (pintype "bidirectional"))
    )
    (net (code "101") (name "unconnected-(U4-PUR-Pad63)") (class "Default")
      (node (ref "U4") (pin "63") (pinfunction "PUR_63") (pintype "bidirectional"))
    )
  )
)
